# sensorNodev2.net
KiCad netlist of a schematic drawn in EAGLE
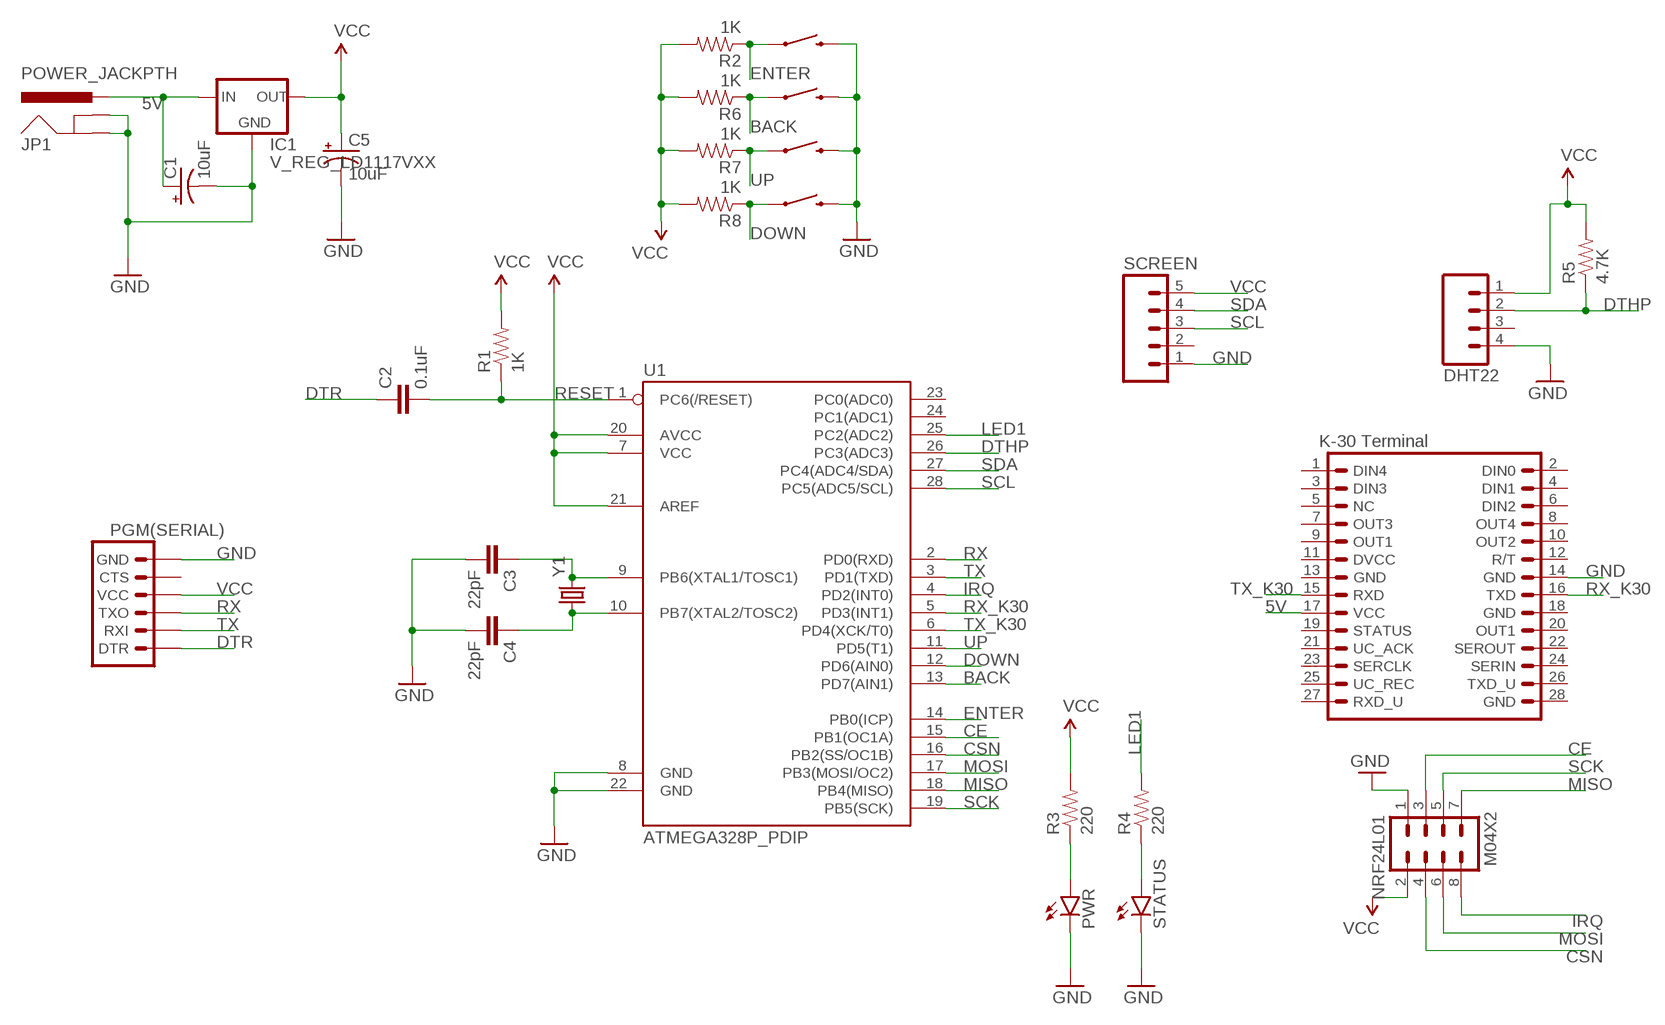
[diagram p0: schematic, sheet 1]

(export (version "E")
  (design (tool "Eeschema 10.0.6"))
  (components
    (comp (ref "BACK")
      (value "SWITCH-MOMENTARY-2PTH")
      (footprint "eagle-import:TACTILE-PTH")
      (libsource (lib "eagle-import") (part "SWITCH-MOMENTARY-2PTH"))
    )
    (comp (ref "C1")
      (value "10uF")
      (footprint "eagle-import:CPOL-RADIAL-10UF-25V")
      (libsource (lib "eagle-import") (part "CAP_POLPTH2"))
    )
    (comp (ref "C2")
      (value "0.1uF")
      (footprint "eagle-import:0603-CAP")
      (libsource (lib "eagle-import") (part "0.1UF-25V(+80/-20%)(0603)"))
    )
    (comp (ref "C3")
      (value "22pF")
      (footprint "eagle-import:0603-CAP")
      (libsource (lib "eagle-import") (part "22PF-50V-5%(0603)"))
    )
    (comp (ref "C4")
      (value "22pF")
      (footprint "eagle-import:0603-CAP")
      (libsource (lib "eagle-import") (part "22PF-50V-5%(0603)"))
    )
    (comp (ref "C5")
      (value "10uF")
      (footprint "eagle-import:CPOL-RADIAL-10UF-25V")
      (libsource (lib "eagle-import") (part "CAP_POLPTH2"))
    )
    (comp (ref "DHT22")
      (value "M04PTH")
      (footprint "eagle-import:1X04")
      (libsource (lib "eagle-import") (part "M04PTH"))
    )
    (comp (ref "DOWN")
      (value "SWITCH-MOMENTARY-2PTH")
      (footprint "eagle-import:TACTILE-PTH")
      (libsource (lib "eagle-import") (part "SWITCH-MOMENTARY-2PTH"))
    )
    (comp (ref "ENTER")
      (value "SWITCH-MOMENTARY-2PTH")
      (footprint "eagle-import:TACTILE-PTH")
      (libsource (lib "eagle-import") (part "SWITCH-MOMENTARY-2PTH"))
    )
    (comp (ref "IC1")
      (value "V_REG_LD1117VXX")
      (footprint "eagle-import:78XXL")
      (libsource (lib "eagle-import") (part "V_REG_LD1117VXX"))
    )
    (comp (ref "JP1")
      (value "POWER_JACKPTH")
      (footprint "eagle-import:POWER_JACK_PTH")
      (libsource (lib "eagle-import") (part "POWER_JACKPTH"))
    )
    (comp (ref "JP3")
      (value "K-30K-30")
      (footprint "eagle-import:K-30")
      (libsource (lib "eagle-import") (part "K-30K-30"))
    )
    (comp (ref "NRF24L01")
      (value "M04X2")
      (footprint "eagle-import:2X4")
      (libsource (lib "eagle-import") (part "M04X2"))
    )
    (comp (ref "PGM(SERIAL)")
      (value "ARDUINO_SERIAL_PROGRAMPTH")
      (footprint "eagle-import:1X06")
      (libsource (lib "eagle-import") (part "ARDUINO_SERIAL_PROGRAMPTH"))
    )
    (comp (ref "PWR")
      (value "LED0603")
      (footprint "eagle-import:LED-0603")
      (libsource (lib "eagle-import") (part "LED0603"))
    )
    (comp (ref "R1")
      (value "1K")
      (footprint "eagle-import:0603-RES")
      (libsource (lib "eagle-import") (part "1KOHM-1/10W-1%(0603)"))
    )
    (comp (ref "R2")
      (value "1K")
      (footprint "eagle-import:0603-RES")
      (libsource (lib "eagle-import") (part "1KOHM-1/10W-1%(0603)"))
    )
    (comp (ref "R3")
      (value "220")
      (footprint "eagle-import:0603-RES")
      (libsource (lib "eagle-import") (part "1KOHM-1/10W-1%(0603)"))
    )
    (comp (ref "R4")
      (value "220")
      (footprint "eagle-import:0603-RES")
      (libsource (lib "eagle-import") (part "1KOHM-1/10W-1%(0603)"))
    )
    (comp (ref "R5")
      (value "4.7K")
      (footprint "eagle-import:0603-RES")
      (libsource (lib "eagle-import") (part "1KOHM-1/10W-1%(0603)"))
    )
    (comp (ref "R6")
      (value "1K")
      (footprint "eagle-import:0603-RES")
      (libsource (lib "eagle-import") (part "1KOHM-1/10W-1%(0603)"))
    )
    (comp (ref "R7")
      (value "1K")
      (footprint "eagle-import:0603-RES")
      (libsource (lib "eagle-import") (part "1KOHM-1/10W-1%(0603)"))
    )
    (comp (ref "R8")
      (value "1K")
      (footprint "eagle-import:0603-RES")
      (libsource (lib "eagle-import") (part "1KOHM-1/10W-1%(0603)"))
    )
    (comp (ref "SCREEN")
      (value "M05PTH")
      (footprint "eagle-import:1X05")
      (libsource (lib "eagle-import") (part "M05PTH"))
    )
    (comp (ref "STATUS")
      (value "LED0603")
      (footprint "eagle-import:LED-0603")
      (libsource (lib "eagle-import") (part "LED0603"))
    )
    (comp (ref "U1")
      (value "ATMEGA328P_PDIP")
      (footprint "eagle-import:DIL28-3")
      (libsource (lib "eagle-import") (part "ATMEGA328P_PDIP"))
    )
    (comp (ref "UP")
      (value "SWITCH-MOMENTARY-2PTH")
      (footprint "eagle-import:TACTILE-PTH")
      (libsource (lib "eagle-import") (part "SWITCH-MOMENTARY-2PTH"))
    )
    (comp (ref "Y1")
      (value "CRYSTALHC49US")
      (footprint "eagle-import:HC49US")
      (libsource (lib "eagle-import") (part "CRYSTALHC49US"))
    )
  )
  (nets
    (net (code "1") (name "/5V") (class "Default")
      (node (ref "C1") (pin "1") (pinfunction "+_1") (pintype "passive"))
      (node (ref "IC1") (pin "OUT") (pinfunction "IN_OUT") (pintype "input"))
      (node (ref "JP1") (pin "PWR") (pinfunction "PWR_PWR") (pintype "bidirectional"))
      (node (ref "JP3") (pin "17") (pinfunction "VCC_17") (pintype "bidirectional"))
    )
    (net (code "2") (name "/BACK") (class "Default")
      (node (ref "BACK") (pin "1") (pinfunction "1_1") (pintype "passive"))
      (node (ref "R6") (pin "1") (pinfunction "1_1") (pintype "passive"))
      (node (ref "U1") (pin "13") (pinfunction "PD7(AIN1)_13") (pintype "bidirectional"))
    )
    (net (code "3") (name "/CE") (class "Default")
      (node (ref "NRF24L01") (pin "3") (pinfunction "3_3") (pintype "passive"))
      (node (ref "U1") (pin "15") (pinfunction "PB1(OC1A)_15") (pintype "bidirectional"))
    )
    (net (code "4") (name "/CSN") (class "Default")
      (node (ref "NRF24L01") (pin "4") (pinfunction "4_4") (pintype "passive"))
      (node (ref "U1") (pin "16") (pinfunction "PB2(SS/OC1B)_16") (pintype "bidirectional"))
    )
    (net (code "5") (name "/DOWN") (class "Default")
      (node (ref "DOWN") (pin "1") (pinfunction "1_1") (pintype "passive"))
      (node (ref "R8") (pin "1") (pinfunction "1_1") (pintype "passive"))
      (node (ref "U1") (pin "12") (pinfunction "PD6(AIN0)_12") (pintype "bidirectional"))
    )
    (net (code "6") (name "/DTHP") (class "Default")
      (node (ref "DHT22") (pin "2") (pinfunction "2_2") (pintype "passive"))
      (node (ref "R5") (pin "1") (pinfunction "1_1") (pintype "passive"))
      (node (ref "U1") (pin "26") (pinfunction "PC3(ADC3)_26") (pintype "bidirectional"))
    )
    (net (code "7") (name "/DTR") (class "Default")
      (node (ref "C2") (pin "1") (pinfunction "1_1") (pintype "passive"))
      (node (ref "PGM(SERIAL)") (pin "1") (pinfunction "DTR_1") (pintype "passive"))
    )
    (net (code "8") (name "/ENTER") (class "Default")
      (node (ref "ENTER") (pin "1") (pinfunction "1_1") (pintype "passive"))
      (node (ref "R2") (pin "1") (pinfunction "1_1") (pintype "passive"))
      (node (ref "U1") (pin "14") (pinfunction "PB0(ICP)_14") (pintype "bidirectional"))
    )
    (net (code "9") (name "/IRQ") (class "Default")
      (node (ref "NRF24L01") (pin "8") (pinfunction "8_8") (pintype "passive"))
      (node (ref "U1") (pin "4") (pinfunction "PD2(INT0)_4") (pintype "bidirectional"))
    )
    (net (code "10") (name "/LED1") (class "Default")
      (node (ref "R4") (pin "2") (pinfunction "2_2") (pintype "passive"))
      (node (ref "U1") (pin "25") (pinfunction "PC2(ADC2)_25") (pintype "bidirectional"))
    )
    (net (code "11") (name "/MISO") (class "Default")
      (node (ref "NRF24L01") (pin "7") (pinfunction "7_7") (pintype "passive"))
      (node (ref "U1") (pin "18") (pinfunction "PB4(MISO)_18") (pintype "bidirectional"))
    )
    (net (code "12") (name "/MOSI") (class "Default")
      (node (ref "NRF24L01") (pin "6") (pinfunction "6_6") (pintype "passive"))
      (node (ref "U1") (pin "17") (pinfunction "PB3(MOSI/OC2)_17") (pintype "bidirectional"))
    )
    (net (code "13") (name "/RESET") (class "Default")
      (node (ref "C2") (pin "2") (pinfunction "2_2") (pintype "passive"))
      (node (ref "R1") (pin "1") (pinfunction "1_1") (pintype "passive"))
      (node (ref "U1") (pin "1") (pinfunction "PC6(/RESET)_1") (pintype "bidirectional"))
    )
    (net (code "14") (name "/RX") (class "Default")
      (node (ref "PGM(SERIAL)") (pin "3") (pinfunction "TXO_3") (pintype "passive"))
      (node (ref "U1") (pin "2") (pinfunction "PD0(RXD)_2") (pintype "bidirectional"))
    )
    (net (code "15") (name "/RX_K30") (class "Default")
      (node (ref "JP3") (pin "16") (pinfunction "TXD_16") (pintype "bidirectional"))
      (node (ref "U1") (pin "5") (pinfunction "PD3(INT1)_5") (pintype "bidirectional"))
    )
    (net (code "16") (name "/SCK") (class "Default")
      (node (ref "NRF24L01") (pin "5") (pinfunction "5_5") (pintype "passive"))
      (node (ref "U1") (pin "19") (pinfunction "PB5(SCK)_19") (pintype "bidirectional"))
    )
    (net (code "17") (name "/SCL") (class "Default")
      (node (ref "SCREEN") (pin "3") (pinfunction "3_3") (pintype "passive"))
      (node (ref "U1") (pin "28") (pinfunction "PC5(ADC5/SCL)_28") (pintype "bidirectional"))
    )
    (net (code "18") (name "/SDA") (class "Default")
      (node (ref "SCREEN") (pin "4") (pinfunction "4_4") (pintype "passive"))
      (node (ref "U1") (pin "27") (pinfunction "PC4(ADC4/SDA)_27") (pintype "bidirectional"))
    )
    (net (code "19") (name "/TX") (class "Default")
      (node (ref "PGM(SERIAL)") (pin "2") (pinfunction "RXI_2") (pintype "passive"))
      (node (ref "U1") (pin "3") (pinfunction "PD1(TXD)_3") (pintype "bidirectional"))
    )
    (net (code "20") (name "/TX_K30") (class "Default")
      (node (ref "JP3") (pin "15") (pinfunction "RXD_15") (pintype "bidirectional"))
      (node (ref "U1") (pin "6") (pinfunction "PD4(XCK/T0)_6") (pintype "bidirectional"))
    )
    (net (code "21") (name "/UP") (class "Default")
      (node (ref "R7") (pin "1") (pinfunction "1_1") (pintype "passive"))
      (node (ref "U1") (pin "11") (pinfunction "PD5(T1)_11") (pintype "bidirectional"))
      (node (ref "UP") (pin "1") (pinfunction "1_1") (pintype "passive"))
    )
    (net (code "22") (name "GND") (class "Default")
      (node (ref "BACK") (pin "3") (pinfunction "2_3") (pintype "passive"))
      (node (ref "C1") (pin "2") (pinfunction "-_2") (pintype "passive"))
      (node (ref "C3") (pin "2") (pinfunction "2_2") (pintype "passive"))
      (node (ref "C4") (pin "2") (pinfunction "2_2") (pintype "passive"))
      (node (ref "C5") (pin "2") (pinfunction "-_2") (pintype "passive"))
      (node (ref "DHT22") (pin "4") (pinfunction "4_4") (pintype "passive"))
      (node (ref "DOWN") (pin "3") (pinfunction "2_3") (pintype "passive"))
      (node (ref "ENTER") (pin "3") (pinfunction "2_3") (pintype "passive"))
      (node (ref "IC1") (pin "IN") (pinfunction "GND_IN") (pintype "input"))
      (node (ref "JP1") (pin "GND") (pinfunction "GND_GND") (pintype "bidirectional"))
      (node (ref "JP1") (pin "GNDBREAK") (pinfunction "GNDBREAK_GNDBREAK") (pintype "bidirectional"))
      (node (ref "JP3") (pin "14") (pinfunction "GND_14") (pintype "bidirectional"))
      (node (ref "NRF24L01") (pin "1") (pinfunction "1_1") (pintype "passive"))
      (node (ref "PGM(SERIAL)") (pin "6") (pinfunction "GND_6") (pintype "passive"))
      (node (ref "PWR") (pin "C") (pinfunction "C_C") (pintype "passive"))
      (node (ref "SCREEN") (pin "1") (pinfunction "1_1") (pintype "passive"))
      (node (ref "STATUS") (pin "C") (pinfunction "C_C") (pintype "passive"))
      (node (ref "U1") (pin "22") (pinfunction "GND_22") (pintype "bidirectional"))
      (node (ref "U1") (pin "8") (pinfunction "GND_8") (pintype "bidirectional"))
      (node (ref "UP") (pin "3") (pinfunction "2_3") (pintype "passive"))
    )
    (net (code "23") (name "Net-(PWR-PadA)") (class "Default")
      (node (ref "PWR") (pin "A") (pinfunction "A_A") (pintype "passive"))
      (node (ref "R3") (pin "1") (pinfunction "1_1") (pintype "passive"))
    )
    (net (code "24") (name "Net-(R4-Pad1)") (class "Default")
      (node (ref "R4") (pin "1") (pinfunction "1_1") (pintype "passive"))
      (node (ref "STATUS") (pin "A") (pinfunction "A_A") (pintype "passive"))
    )
    (net (code "25") (name "Net-(U1-PB6(XTAL1{slash}TOSC1))") (class "Default")
      (node (ref "C3") (pin "1") (pinfunction "1_1") (pintype "passive"))
      (node (ref "U1") (pin "9") (pinfunction "PB6(XTAL1/TOSC1)_9") (pintype "bidirectional"))
      (node (ref "Y1") (pin "2") (pinfunction "2_2") (pintype "passive"))
    )
    (net (code "26") (name "Net-(U1-PB7(XTAL2{slash}TOSC2))") (class "Default")
      (node (ref "C4") (pin "1") (pinfunction "1_1") (pintype "passive"))
      (node (ref "U1") (pin "10") (pinfunction "PB7(XTAL2/TOSC2)_10") (pintype "bidirectional"))
      (node (ref "Y1") (pin "1") (pinfunction "1_1") (pintype "passive"))
    )
    (net (code "27") (name "VCC") (class "Default")
      (node (ref "C5") (pin "1") (pinfunction "+_1") (pintype "passive"))
      (node (ref "DHT22") (pin "1") (pinfunction "1_1") (pintype "passive"))
      (node (ref "IC1") (pin "GND") (pinfunction "OUT_GND") (pintype "output"))
      (node (ref "NRF24L01") (pin "2") (pinfunction "2_2") (pintype "passive"))
      (node (ref "PGM(SERIAL)") (pin "4") (pinfunction "VCC_4") (pintype "passive"))
      (node (ref "R1") (pin "2") (pinfunction "2_2") (pintype "passive"))
      (node (ref "R2") (pin "2") (pinfunction "2_2") (pintype "passive"))
      (node (ref "R3") (pin "2") (pinfunction "2_2") (pintype "passive"))
      (node (ref "R5") (pin "2") (pinfunction "2_2") (pintype "passive"))
      (node (ref "R6") (pin "2") (pinfunction "2_2") (pintype "passive"))
      (node (ref "R7") (pin "2") (pinfunction "2_2") (pintype "passive"))
      (node (ref "R8") (pin "2") (pinfunction "2_2") (pintype "passive"))
      (node (ref "SCREEN") (pin "5") (pinfunction "5_5") (pintype "passive"))
      (node (ref "U1") (pin "20") (pinfunction "AVCC_20") (pintype "bidirectional"))
      (node (ref "U1") (pin "21") (pinfunction "AREF_21") (pintype "bidirectional"))
      (node (ref "U1") (pin "7") (pinfunction "VCC_7") (pintype "bidirectional"))
    )
    (net (code "28") (name "unconnected-(DHT22-Pad3)") (class "Default")
      (node (ref "DHT22") (pin "3") (pinfunction "3_3") (pintype "passive"))
    )
    (net (code "29") (name "unconnected-(JP3-DIN0-Pad2)") (class "Default")
      (node (ref "JP3") (pin "2") (pinfunction "DIN0_2") (pintype "bidirectional"))
    )
    (net (code "30") (name "unconnected-(JP3-DIN1-Pad4)") (class "Default")
      (node (ref "JP3") (pin "4") (pinfunction "DIN1_4") (pintype "bidirectional"))
    )
    (net (code "31") (name "unconnected-(JP3-DIN2-Pad6)") (class "Default")
      (node (ref "JP3") (pin "6") (pinfunction "DIN2_6") (pintype "bidirectional"))
    )
    (net (code "32") (name "unconnected-(JP3-DIN3-Pad3)") (class "Default")
      (node (ref "JP3") (pin "3") (pinfunction "DIN3_3") (pintype "bidirectional"))
    )
    (net (code "33") (name "unconnected-(JP3-DIN4-Pad1)") (class "Default")
      (node (ref "JP3") (pin "1") (pinfunction "DIN4_1") (pintype "bidirectional"))
    )
    (net (code "34") (name "unconnected-(JP3-DVCC-Pad11)") (class "Default")
      (node (ref "JP3") (pin "11") (pinfunction "DVCC_11") (pintype "bidirectional"))
    )
    (net (code "35") (name "unconnected-(JP3-GND-Pad13)") (class "Default")
      (node (ref "JP3") (pin "13") (pinfunction "GND_13") (pintype "bidirectional"))
    )
    (net (code "36") (name "unconnected-(JP3-GND-Pad18)") (class "Default")
      (node (ref "JP3") (pin "18") (pinfunction "GND_18") (pintype "bidirectional"))
    )
    (net (code "37") (name "unconnected-(JP3-GND-Pad28)") (class "Default")
      (node (ref "JP3") (pin "28") (pinfunction "GND_28") (pintype "bidirectional"))
    )
    (net (code "38") (name "unconnected-(JP3-NC-Pad5)") (class "Default")
      (node (ref "JP3") (pin "5") (pinfunction "NC_5") (pintype "bidirectional"))
    )
    (net (code "39") (name "unconnected-(JP3-OUT1-Pad9)") (class "Default")
      (node (ref "JP3") (pin "9") (pinfunction "OUT1_9") (pintype "bidirectional"))
    )
    (net (code "40") (name "unconnected-(JP3-OUT1-Pad20)") (class "Default")
      (node (ref "JP3") (pin "20") (pinfunction "OUT1_20") (pintype "bidirectional"))
    )
    (net (code "41") (name "unconnected-(JP3-OUT2-Pad10)") (class "Default")
      (node (ref "JP3") (pin "10") (pinfunction "OUT2_10") (pintype "bidirectional"))
    )
    (net (code "42") (name "unconnected-(JP3-OUT3-Pad7)") (class "Default")
      (node (ref "JP3") (pin "7") (pinfunction "OUT3_7") (pintype "bidirectional"))
    )
    (net (code "43") (name "unconnected-(JP3-OUT4-Pad8)") (class "Default")
      (node (ref "JP3") (pin "8") (pinfunction "OUT4_8") (pintype "bidirectional"))
    )
    (net (code "44") (name "unconnected-(JP3-RXD_U-Pad27)") (class "Default")
      (node (ref "JP3") (pin "27") (pinfunction "RXD_U_27") (pintype "bidirectional"))
    )
    (net (code "45") (name "unconnected-(JP3-R{slash}T-Pad12)") (class "Default")
      (node (ref "JP3") (pin "12") (pinfunction "R/T_12") (pintype "bidirectional"))
    )
    (net (code "46") (name "unconnected-(JP3-SERCLK-Pad23)") (class "Default")
      (node (ref "JP3") (pin "23") (pinfunction "SERCLK_23") (pintype "bidirectional"))
    )
    (net (code "47") (name "unconnected-(JP3-SERIN-Pad24)") (class "Default")
      (node (ref "JP3") (pin "24") (pinfunction "SERIN_24") (pintype "bidirectional"))
    )
    (net (code "48") (name "unconnected-(JP3-SEROUT-Pad22)") (class "Default")
      (node (ref "JP3") (pin "22") (pinfunction "SEROUT_22") (pintype "bidirectional"))
    )
    (net (code "49") (name "unconnected-(JP3-STATUS-Pad19)") (class "Default")
      (node (ref "JP3") (pin "19") (pinfunction "STATUS_19") (pintype "bidirectional"))
    )
    (net (code "50") (name "unconnected-(JP3-TXD_U-Pad26)") (class "Default")
      (node (ref "JP3") (pin "26") (pinfunction "TXD_U_26") (pintype "bidirectional"))
    )
    (net (code "51") (name "unconnected-(JP3-UC_ACK-Pad21)") (class "Default")
      (node (ref "JP3") (pin "21") (pinfunction "UC_ACK_21") (pintype "bidirectional"))
    )
    (net (code "52") (name "unconnected-(JP3-UC_REC-Pad25)") (class "Default")
      (node (ref "JP3") (pin "25") (pinfunction "UC_REC_25") (pintype "bidirectional"))
    )
    (net (code "53") (name "unconnected-(PGM(SERIAL)-CTS-Pad5)") (class "Default")
      (node (ref "PGM(SERIAL)") (pin "5") (pinfunction "CTS_5") (pintype "passive"))
    )
    (net (code "54") (name "unconnected-(SCREEN-Pad2)") (class "Default")
      (node (ref "SCREEN") (pin "2") (pinfunction "2_2") (pintype "passive"))
    )
    (net (code "55") (name "unconnected-(U1-PC0(ADC0)-Pad23)") (class "Default")
      (node (ref "U1") (pin "23") (pinfunction "PC0(ADC0)_23") (pintype "bidirectional"))
    )
    (net (code "56") (name "unconnected-(U1-PC1(ADC1)-Pad24)") (class "Default")
      (node (ref "U1") (pin "24") (pinfunction "PC1(ADC1)_24") (pintype "bidirectional"))
    )
  )
)
